# CH32F_V208W-R0.net
KiCad netlist of a schematic drawn in Altium Designer
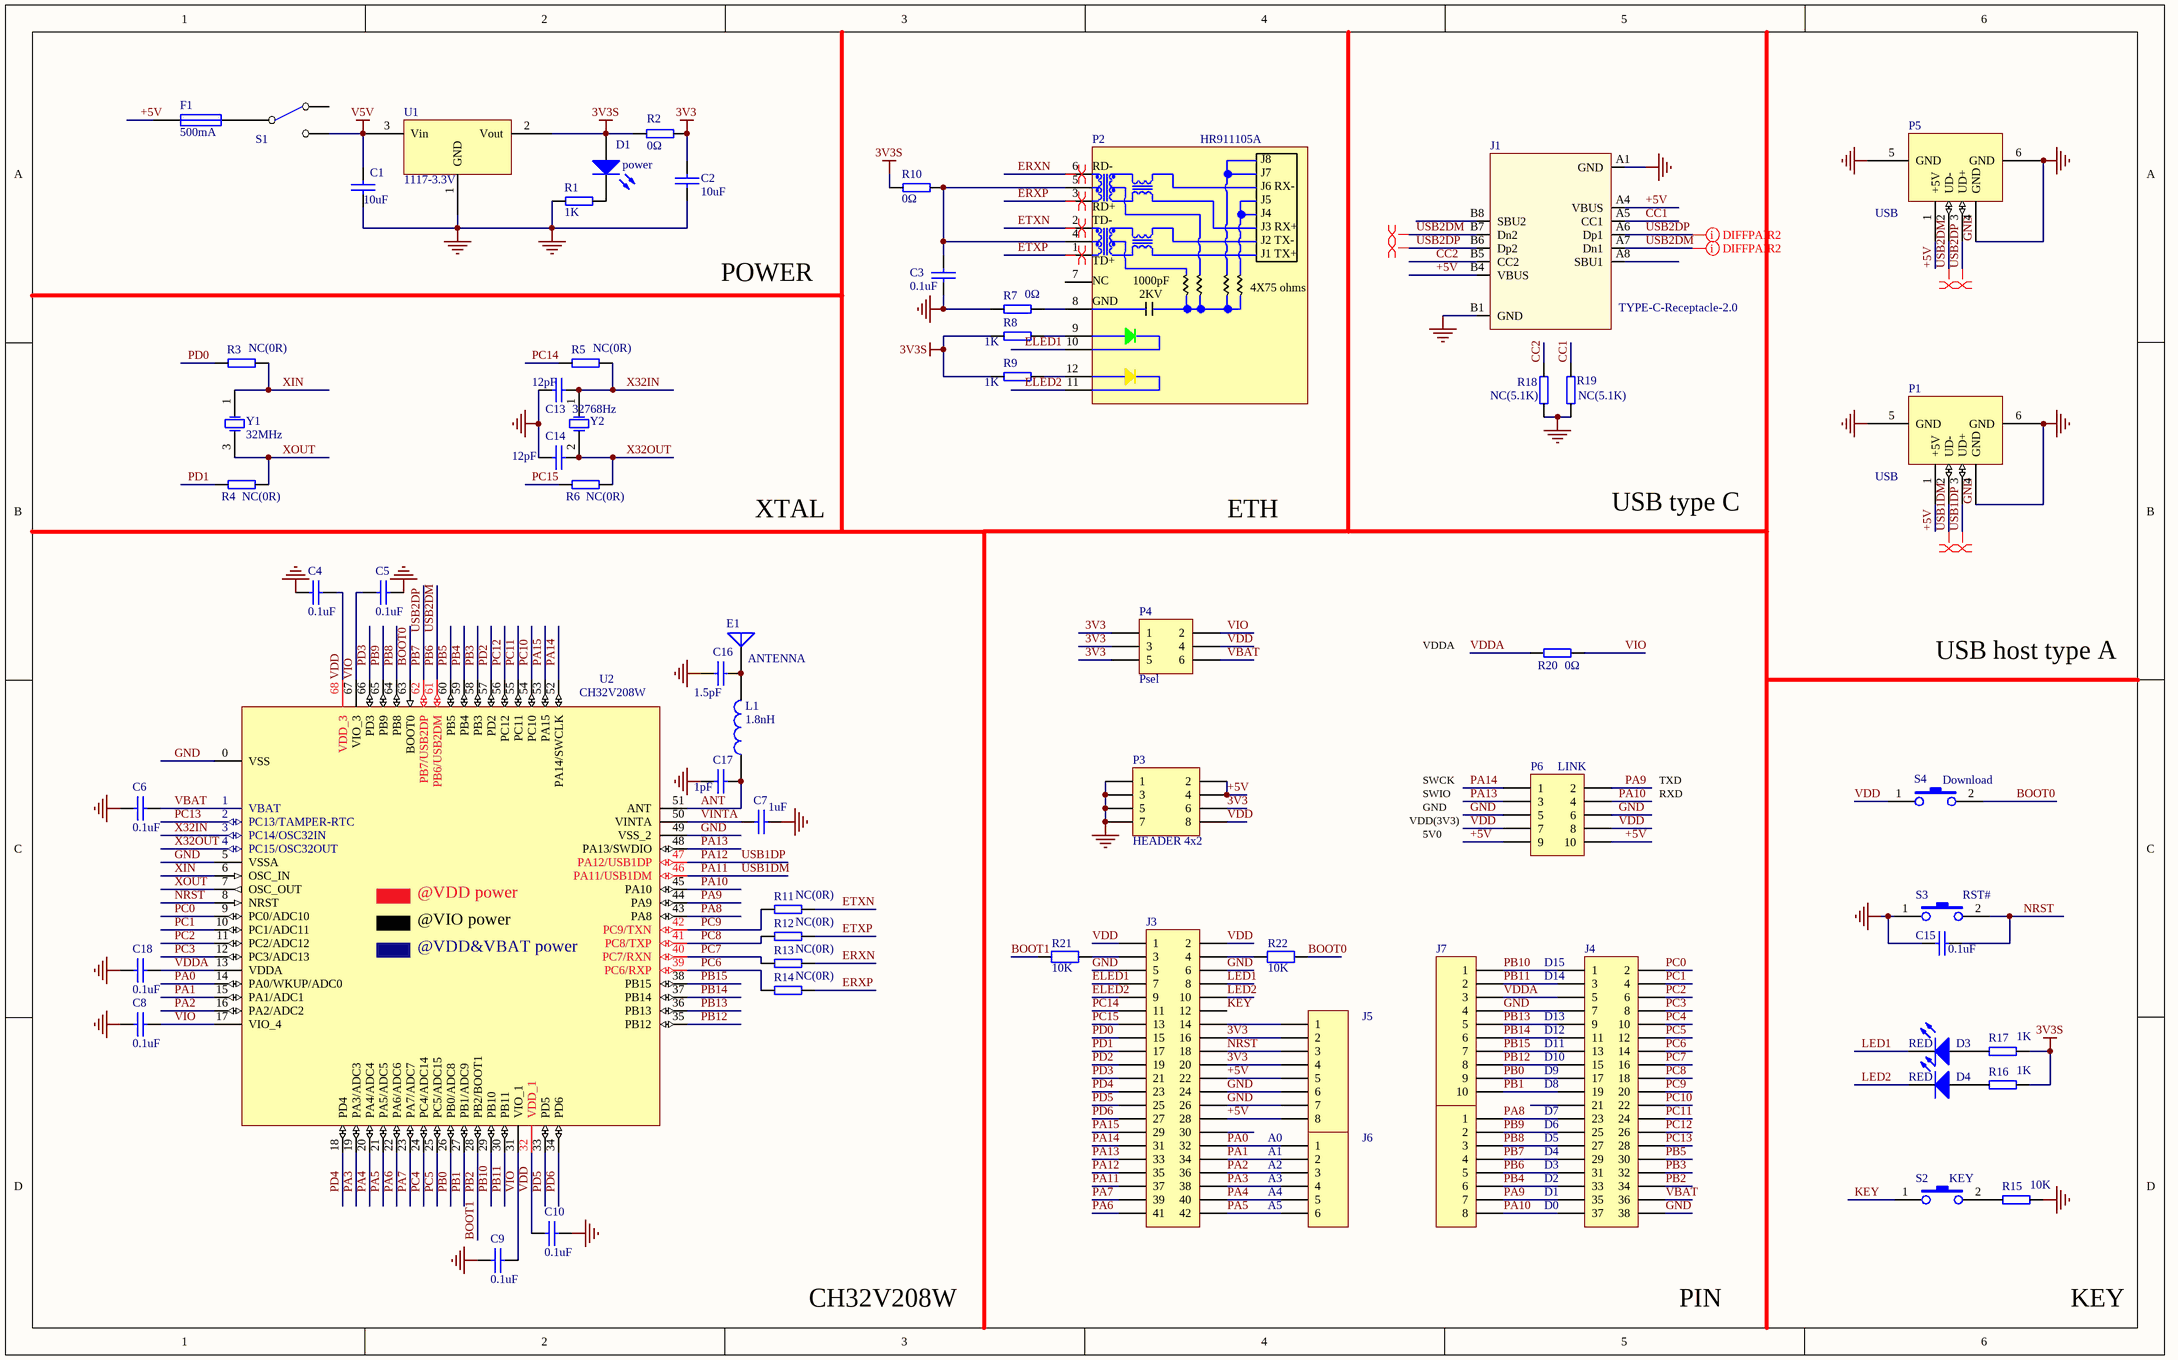
[diagram p0: CH32F&V208W-R0.SchDoc]

(export (version "E")
  (design (tool "Eeschema 10.0.6"))
  (components
    (comp (ref "C1")
      (value "10uF")
      (footprint "3216_C")
      (description "Capacitor")
      (libsource (lib "*") (part "CAP"))
    )
    (comp (ref "C2")
      (value "10uF")
      (footprint "0603_C")
      (description "Capacitor")
      (libsource (lib "*") (part "CAP"))
    )
    (comp (ref "C3")
      (value "0.1uF")
      (footprint "0603_C")
      (description "Capacitor")
      (libsource (lib "*") (part "CAP"))
    )
    (comp (ref "C4")
      (value "0.1uF")
      (footprint "0603_C")
      (description "Capacitor")
      (libsource (lib "") (part "CAP_1"))
    )
    (comp (ref "C5")
      (value "0.1uF")
      (footprint "0603_C")
      (description "Capacitor")
      (libsource (lib "") (part "CAP_1"))
    )
    (comp (ref "C6")
      (value "0.1uF")
      (footprint "0603_C")
      (description "Capacitor")
      (libsource (lib "") (part "CAP_1"))
    )
    (comp (ref "C7")
      (value "1uF")
      (footprint "0603_C")
      (description "Capacitor")
      (libsource (lib "") (part "CAP_1"))
    )
    (comp (ref "C8")
      (value "0.1uF")
      (footprint "0603_C")
      (description "Capacitor")
      (libsource (lib "") (part "CAP_1"))
    )
    (comp (ref "C9")
      (value "0.1uF")
      (footprint "0603_C")
      (description "Capacitor")
      (libsource (lib "") (part "CAP_1"))
    )
    (comp (ref "C10")
      (value "0.1uF")
      (footprint "0603_C")
      (description "Capacitor")
      (libsource (lib "") (part "CAP_1"))
    )
    (comp (ref "C13")
      (value "12pF")
      (footprint "0603_C")
      (description "Capacitor")
      (libsource (lib "*") (part "CAP"))
    )
    (comp (ref "C14")
      (value "12pF")
      (footprint "0603_C")
      (description "Capacitor")
      (libsource (lib "*") (part "CAP"))
    )
    (comp (ref "C15")
      (value "0.1uF")
      (footprint "0603_C")
      (description "Capacitor")
      (libsource (lib "") (part "CAP_1"))
    )
    (comp (ref "C16")
      (value "1.5pF")
      (footprint "0603_C")
      (description "Capacitor")
      (libsource (lib "") (part "CAP_1"))
    )
    (comp (ref "C17")
      (value "1pF")
      (footprint "0603_C")
      (description "Capacitor")
      (libsource (lib "") (part "CAP_1"))
    )
    (comp (ref "C18")
      (value "0.1uF")
      (footprint "0603_C")
      (description "Capacitor")
      (libsource (lib "") (part "CAP_1"))
    )
    (comp (ref "D1")
      (value "power")
      (footprint "0603+")
      (description "Typical INFRARED GaAs LED")
      (fields (field (name "PUBLISHER") "Altium Limited"))
      (libsource (lib "*") (part "LED0"))
    )
    (comp (ref "D3")
      (value "RED")
      (footprint "0603+")
      (description "Typical INFRARED GaAs LED")
      (fields (field (name "PUBLISHER") "Altium Limited"))
      (libsource (lib "*") (part "LED0"))
    )
    (comp (ref "D4")
      (value "RED")
      (footprint "0603+")
      (description "Typical INFRARED GaAs LED")
      (fields (field (name "PUBLISHER") "Altium Limited"))
      (libsource (lib "*") (part "LED0"))
    )
    (comp (ref "E1")
      (value "ANTENNA")
      (footprint "MYPCB:ANT-F-1-2.4G-1.6")
      (description "Generic Antenna")
      (libsource (lib "*") (part "ANTENNA"))
    )
    (comp (ref "F1")
      (value "500mA")
      (footprint "0603")
      (description "Fuse")
      (libsource (lib "wch_sch_others") (part "FUSE1"))
    )
    (comp (ref "J1")
      (value "TYPE-C-Receptacle-2.0")
      (footprint "TYPE-C-Receptacle-2.0")
      (description "Type-C USB2.0 母座")
      (libsource (lib "Miscellaneous SCH Lib") (part "TYPE-C-Receptacle-2.0"))
    )
    (comp (ref "J3")
      (value "Header 21X2")
      (footprint "IDC42-2.54mm")
      (description "Header, 21-Pin, Dual row")
      (fields (field (name "PUBLISHER") "Altium Limited"))
      (libsource (lib "PCB_Project") (part "Header 21X2"))
    )
    (comp (ref "J4")
      (value "Header 19X2")
      (footprint "IDC38-2.54mm")
      (description "Header, 19-Pin, Dual row")
      (fields (field (name "PUBLISHER") "Altium Limited"))
      (libsource (lib "Miscellaneous Connectors") (part "Header 19X2"))
    )
    (comp (ref "J5")
      (value "Header 8")
      (footprint "SIP8-2.54mm")
      (description "Header, 8-Pin")
      (fields (field (name "PUBLISHER") "Altium Limited"))
      (libsource (lib "Miscellaneous Connectors") (part "Header 8"))
    )
    (comp (ref "J6")
      (value "Header 6")
      (footprint "SIP6-2.54MM")
      (description "Header, 6-Pin")
      (fields (field (name "PUBLISHER") "Altium Limited"))
      (libsource (lib "Miscellaneous Connectors") (part "Header 6"))
    )
    (comp (ref "J7")
      (value "Header 10")
      (footprint "SIP10-2.54mm")
      (description "Header, 10-Pin")
      (fields (field (name "PUBLISHER") "Altium Limited"))
      (libsource (lib "Miscellaneous Connectors") (part "Header 10"))
    )
    (comp (ref "J8")
      (value "Header 8")
      (footprint "SIP8-2.54mm")
      (description "Header, 8-Pin")
      (fields (field (name "PUBLISHER") "Altium Limited"))
      (libsource (lib "") (part "Header 8_1"))
    )
    (comp (ref "L1") (value "1.8nH") (footprint "0603") (libsource (lib "*") (part "INDUCTOR")))
    (comp (ref "P1")
      (value "USB")
      (footprint "USBAF")
      (description "USB Port")
      (libsource (lib "*") (part "USB"))
    )
    (comp (ref "P2") (value "HR911105A") (footprint "HR911105A") (libsource (lib "*") (part "HR911105A")))
    (comp (ref "P3")
      (value "HEADER 4x2")
      (footprint "MYPCB:IDC8-2.54mm")
      (description "Header, 4-Pin, Dual row")
      (libsource (lib "wch_sch_others") (part "HEADER 4x2"))
    )
    (comp (ref "P4")
      (value "Psel")
      (footprint "IDC6-2.54mm")
      (description "Header, 3-Pin, Dual row, Right Angle")
      (fields (field (name "PUBLISHER") "Altium Limited"))
      (libsource (lib "Miscellaneous Connectors") (part "Header 3X2H"))
    )
    (comp (ref "P5")
      (value "USB")
      (footprint "USBAF")
      (description "USB Port")
      (libsource (lib "*") (part "USB"))
    )
    (comp (ref "P6")
      (value "LINK")
      (footprint "IDC10-2.54mm")
      (description "Header, 5-Pin, Dual row, Right Angle")
      (fields (field (name "PUBLISHER") "Altium Limited"))
      (libsource (lib "Miscellaneous Connectors") (part "Header 5X2H"))
    )
    (comp (ref "R1") (value "1K") (footprint "0603") (libsource (lib "wch_sch_others") (part "RES")))
    (comp (ref "R2") (value "0Ω") (footprint "0603") (libsource (lib "wch_sch_others") (part "RES")))
    (comp (ref "R3") (value "NC(0R)") (footprint "0603") (libsource (lib "wch_sch_others") (part "RES")))
    (comp (ref "R4") (value "NC(0R)") (footprint "0603") (libsource (lib "wch_sch_others") (part "RES")))
    (comp (ref "R5") (value "NC(0R)") (footprint "0603") (libsource (lib "wch_sch_others") (part "RES")))
    (comp (ref "R6") (value "NC(0R)") (footprint "0603") (libsource (lib "wch_sch_others") (part "RES")))
    (comp (ref "R7") (value "0Ω") (footprint "0603") (libsource (lib "wch_sch_others") (part "RES")))
    (comp (ref "R8") (value "1K") (footprint "0603") (libsource (lib "wch_sch_others") (part "RES")))
    (comp (ref "R9") (value "1K") (footprint "0603") (libsource (lib "wch_sch_others") (part "RES")))
    (comp (ref "R10") (value "0Ω") (footprint "0603") (libsource (lib "wch_sch_others") (part "RES")))
    (comp (ref "R11") (value "NC(0R)") (footprint "0603") (libsource (lib "wch_sch_others") (part "RES")))
    (comp (ref "R12") (value "NC(0R)") (footprint "0603") (libsource (lib "wch_sch_others") (part "RES")))
    (comp (ref "R13") (value "NC(0R)") (footprint "0603") (libsource (lib "wch_sch_others") (part "RES")))
    (comp (ref "R14") (value "NC(0R)") (footprint "0603") (libsource (lib "wch_sch_others") (part "RES")))
    (comp (ref "R15") (value "10K") (footprint "0603") (libsource (lib "wch_sch_others") (part "RES")))
    (comp (ref "R16") (value "1K") (footprint "0603") (libsource (lib "wch_sch_others") (part "RES")))
    (comp (ref "R17") (value "1K") (footprint "0603") (libsource (lib "wch_sch_others") (part "RES")))
    (comp (ref "R18") (value "NC(5.1K)") (footprint "0603") (libsource (lib "wch_sch_others") (part "RES")))
    (comp (ref "R19") (value "NC(5.1K)") (footprint "0603") (libsource (lib "wch_sch_others") (part "RES")))
    (comp (ref "R20") (value "0Ω") (footprint "0603") (libsource (lib "*") (part "R")))
    (comp (ref "R21")
      (value "10K")
      (footprint "0603")
      (description "Resistor")
      (libsource (lib "Miscellaneous Devices") (part "Res2"))
    )
    (comp (ref "R22")
      (value "10K")
      (footprint "0603")
      (description "Resistor")
      (libsource (lib "Miscellaneous Devices") (part "Res2"))
    )
    (comp (ref "S1") (value "SW SPDT") (footprint "KEY_B") (libsource (lib "*") (part "SW SPDT")))
    (comp (ref "S2")
      (value "KEY")
      (footprint "SMD_6.1x3.65x2.5mm-KEY")
      (libsource (lib "wch_sch_others") (part "KEY1"))
    )
    (comp (ref "S3")
      (value "RST#")
      (footprint "SMD_6.1x3.65x2.5mm-KEY")
      (libsource (lib "wch_sch_others") (part "KEY1"))
    )
    (comp (ref "S4")
      (value "Download")
      (footprint "SMD_6.1x3.65x2.5mm-KEY")
      (libsource (lib "wch_sch_others") (part "KEY1"))
    )
    (comp (ref "U1")
      (value "1117-3.3V")
      (footprint "SOT-223")
      (libsource (lib "wch_sch_others") (part "1117-3.3V"))
    )
    (comp (ref "U2")
      (value "CH32V208W")
      (footprint "QFN68_8x8")
      (description "RISC-V BLE5.3 MCU, 10M Ethernet, 2*USB, CAN")
      (libsource (lib "CHXXX") (part "CH32V208W"))
    )
    (comp (ref "Y1")
      (value "32MHz")
      (footprint "XT3225")
      (description "Crystal Oscillator")
      (fields (field (name "PUBLISHER") "Altium Limited"))
      (libsource (lib "") (part "XTAL_1"))
    )
    (comp (ref "Y2")
      (value "32768Hz")
      (footprint "FC-135")
      (description "Crystal Oscillator")
      (fields (field (name "PUBLISHER") "Altium Limited"))
      (libsource (lib "*") (part "XTAL"))
    )
  )
  (nets
    (net (code "1") (name "/+5V") (class "Default")
      (node (ref "F1") (pin "1") (pinfunction "1_1") (pintype "passive"))
      (node (ref "J1") (pin "A4") (pinfunction "VBUS_A4") (pintype "passive"))
      (node (ref "J1") (pin "B4") (pinfunction "VBUS_B4") (pintype "passive"))
      (node (ref "J3") (pin "22") (pinfunction "22_22") (pintype "passive"))
      (node (ref "J3") (pin "28") (pinfunction "28_28") (pintype "passive"))
      (node (ref "J5") (pin "5") (pinfunction "5_5") (pintype "passive"))
      (node (ref "J5") (pin "8") (pinfunction "8_8") (pintype "passive"))
      (node (ref "P1") (pin "1") (pinfunction "+5V_1") (pintype "power_in"))
      (node (ref "P3") (pin "2") (pinfunction "2_2") (pintype "passive"))
      (node (ref "P3") (pin "4") (pinfunction "4_4") (pintype "passive"))
      (node (ref "P5") (pin "1") (pinfunction "+5V_1") (pintype "power_in"))
      (node (ref "P6") (pin "10") (pinfunction "10_10") (pintype "passive"))
      (node (ref "P6") (pin "9") (pinfunction "9_9") (pintype "passive"))
    )
    (net (code "2") (name "/ANT") (class "Default")
      (node (ref "C17") (pin "2") (pinfunction "2_2") (pintype "passive"))
      (node (ref "L1") (pin "1") (pinfunction "1_1") (pintype "passive"))
      (node (ref "U2") (pin "51") (pinfunction "ANT_51") (pintype "power_in"))
    )
    (net (code "3") (name "/BOOT0") (class "Default")
      (node (ref "R22") (pin "2") (pinfunction "2_2") (pintype "passive"))
      (node (ref "S4") (pin "2") (pinfunction "2_2") (pintype "passive"))
      (node (ref "U2") (pin "63") (pinfunction "BOOT0_63") (pintype "input"))
    )
    (net (code "4") (name "/BOOT1") (class "Default")
      (node (ref "J4") (pin "34") (pinfunction "34_34") (pintype "passive"))
      (node (ref "R21") (pin "1") (pinfunction "1_1") (pintype "passive"))
      (node (ref "U2") (pin "28") (pinfunction "PB2/BOOT1_28") (pintype "bidirectional"))
    )
    (net (code "5") (name "/CC1") (class "Default")
      (node (ref "J1") (pin "A5") (pinfunction "CC1_A5") (pintype "passive"))
      (node (ref "R19") (pin "1") (pintype "passive"))
    )
    (net (code "6") (name "/CC2") (class "Default")
      (node (ref "J1") (pin "B5") (pinfunction "CC2_B5") (pintype "passive"))
      (node (ref "R18") (pin "1") (pintype "passive"))
    )
    (net (code "7") (name "/ELED1") (class "Default")
      (node (ref "J3") (pin "7") (pinfunction "7_7") (pintype "passive"))
      (node (ref "P2") (pin "10") (pintype "passive"))
    )
    (net (code "8") (name "/ELED2") (class "Default")
      (node (ref "J3") (pin "9") (pinfunction "9_9") (pintype "passive"))
      (node (ref "P2") (pin "11") (pintype "passive"))
    )
    (net (code "9") (name "/ERXN") (class "Default")
      (node (ref "P2") (pin "6") (pintype "passive"))
      (node (ref "R13") (pin "2") (pintype "passive"))
    )
    (net (code "10") (name "/ERXP") (class "Default")
      (node (ref "P2") (pin "3") (pintype "passive"))
      (node (ref "R14") (pin "2") (pintype "passive"))
    )
    (net (code "11") (name "/ETXN") (class "Default")
      (node (ref "P2") (pin "2") (pintype "passive"))
      (node (ref "R11") (pin "2") (pintype "passive"))
    )
    (net (code "12") (name "/ETXP") (class "Default")
      (node (ref "P2") (pin "1") (pintype "passive"))
      (node (ref "R12") (pin "2") (pintype "passive"))
    )
    (net (code "13") (name "/KEY") (class "Default")
      (node (ref "J3") (pin "12") (pinfunction "12_12") (pintype "passive"))
      (node (ref "S2") (pin "1") (pinfunction "1_1") (pintype "passive"))
    )
    (net (code "14") (name "/LED1") (class "Default")
      (node (ref "D3") (pin "2") (pinfunction "K_2") (pintype "passive"))
      (node (ref "J3") (pin "8") (pinfunction "8_8") (pintype "passive"))
    )
    (net (code "15") (name "/LED2") (class "Default")
      (node (ref "D4") (pin "2") (pinfunction "K_2") (pintype "passive"))
      (node (ref "J3") (pin "10") (pinfunction "10_10") (pintype "passive"))
    )
    (net (code "16") (name "/NRST") (class "Default")
      (node (ref "C15") (pin "2") (pinfunction "2_2") (pintype "passive"))
      (node (ref "J3") (pin "18") (pinfunction "18_18") (pintype "passive"))
      (node (ref "J5") (pin "3") (pinfunction "3_3") (pintype "passive"))
      (node (ref "S3") (pin "2") (pinfunction "2_2") (pintype "passive"))
      (node (ref "U2") (pin "8") (pinfunction "NRST_8") (pintype "input"))
    )
    (net (code "17") (name "/PA0") (class "Default")
      (node (ref "J3") (pin "32") (pinfunction "32_32") (pintype "passive"))
      (node (ref "J6") (pin "1") (pinfunction "1_1") (pintype "passive"))
      (node (ref "U2") (pin "14") (pinfunction "PA0/WKUP/ADC0_14") (pintype "bidirectional"))
    )
    (net (code "18") (name "/PA1") (class "Default")
      (node (ref "J3") (pin "34") (pinfunction "34_34") (pintype "passive"))
      (node (ref "J6") (pin "2") (pinfunction "2_2") (pintype "passive"))
      (node (ref "U2") (pin "15") (pinfunction "PA1/ADC1_15") (pintype "bidirectional"))
    )
    (net (code "19") (name "/PA2") (class "Default")
      (node (ref "J3") (pin "36") (pinfunction "36_36") (pintype "passive"))
      (node (ref "J6") (pin "3") (pinfunction "3_3") (pintype "passive"))
      (node (ref "U2") (pin "16") (pinfunction "PA2/ADC2_16") (pintype "bidirectional"))
    )
    (net (code "20") (name "/PA3") (class "Default")
      (node (ref "J3") (pin "38") (pinfunction "38_38") (pintype "passive"))
      (node (ref "J6") (pin "4") (pinfunction "4_4") (pintype "passive"))
      (node (ref "U2") (pin "19") (pinfunction "PA3/ADC3_19") (pintype "bidirectional"))
    )
    (net (code "21") (name "/PA4") (class "Default")
      (node (ref "J3") (pin "40") (pinfunction "40_40") (pintype "passive"))
      (node (ref "J6") (pin "5") (pinfunction "5_5") (pintype "passive"))
      (node (ref "U2") (pin "20") (pinfunction "PA4/ADC4_20") (pintype "bidirectional"))
    )
    (net (code "22") (name "/PA5") (class "Default")
      (node (ref "J3") (pin "42") (pinfunction "42_42") (pintype "passive"))
      (node (ref "J6") (pin "6") (pinfunction "6_6") (pintype "passive"))
      (node (ref "U2") (pin "21") (pinfunction "PA5/ADC5_21") (pintype "bidirectional"))
    )
    (net (code "23") (name "/PA6") (class "Default")
      (node (ref "J3") (pin "41") (pinfunction "41_41") (pintype "passive"))
      (node (ref "U2") (pin "22") (pinfunction "PA6/ADC6_22") (pintype "bidirectional"))
    )
    (net (code "24") (name "/PA7") (class "Default")
      (node (ref "J3") (pin "39") (pinfunction "39_39") (pintype "passive"))
      (node (ref "U2") (pin "23") (pinfunction "PA7/ADC7_23") (pintype "bidirectional"))
    )
    (net (code "25") (name "/PA8") (class "Default")
      (node (ref "J4") (pin "23") (pinfunction "23_23") (pintype "passive"))
      (node (ref "J8") (pin "1") (pinfunction "1_1") (pintype "passive"))
      (node (ref "U2") (pin "43") (pinfunction "PA8_43") (pintype "bidirectional"))
    )
    (net (code "26") (name "/PA9") (class "Default")
      (node (ref "J4") (pin "35") (pinfunction "35_35") (pintype "passive"))
      (node (ref "J8") (pin "7") (pinfunction "7_7") (pintype "passive"))
      (node (ref "P6") (pin "2") (pinfunction "2_2") (pintype "passive"))
      (node (ref "U2") (pin "44") (pinfunction "PA9_44") (pintype "bidirectional"))
    )
    (net (code "27") (name "/PA10") (class "Default")
      (node (ref "J4") (pin "37") (pinfunction "37_37") (pintype "passive"))
      (node (ref "J8") (pin "8") (pinfunction "8_8") (pintype "passive"))
      (node (ref "P6") (pin "4") (pinfunction "4_4") (pintype "passive"))
      (node (ref "U2") (pin "45") (pinfunction "PA10_45") (pintype "bidirectional"))
    )
    (net (code "28") (name "/PA11") (class "Default")
      (node (ref "J3") (pin "37") (pinfunction "37_37") (pintype "passive"))
      (node (ref "P1") (pin "2") (pinfunction "UD-_2") (pintype "bidirectional"))
      (node (ref "U2") (pin "46") (pinfunction "PA11/USB1DM_46") (pintype "bidirectional"))
    )
    (net (code "29") (name "/PA12") (class "Default")
      (node (ref "J3") (pin "35") (pinfunction "35_35") (pintype "passive"))
      (node (ref "P1") (pin "3") (pinfunction "UD+_3") (pintype "bidirectional"))
      (node (ref "U2") (pin "47") (pinfunction "PA12/USB1DP_47") (pintype "bidirectional"))
    )
    (net (code "30") (name "/PA13") (class "Default")
      (node (ref "J3") (pin "33") (pinfunction "33_33") (pintype "passive"))
      (node (ref "P6") (pin "3") (pinfunction "3_3") (pintype "passive"))
      (node (ref "U2") (pin "48") (pinfunction "PA13/SWDIO_48") (pintype "bidirectional"))
    )
    (net (code "31") (name "/PA14") (class "Default")
      (node (ref "J3") (pin "31") (pinfunction "31_31") (pintype "passive"))
      (node (ref "P6") (pin "1") (pinfunction "1_1") (pintype "passive"))
      (node (ref "U2") (pin "52") (pinfunction "PA14/SWCLK_52") (pintype "bidirectional"))
    )
    (net (code "32") (name "/PA15") (class "Default")
      (node (ref "J3") (pin "29") (pinfunction "29_29") (pintype "passive"))
      (node (ref "U2") (pin "53") (pinfunction "PA15_53") (pintype "bidirectional"))
    )
    (net (code "33") (name "/PB0") (class "Default")
      (node (ref "J4") (pin "17") (pinfunction "17_17") (pintype "passive"))
      (node (ref "J7") (pin "9") (pinfunction "9_9") (pintype "passive"))
      (node (ref "U2") (pin "26") (pinfunction "PB0/ADC8_26") (pintype "bidirectional"))
    )
    (net (code "34") (name "/PB1") (class "Default")
      (node (ref "J4") (pin "19") (pinfunction "19_19") (pintype "passive"))
      (node (ref "J7") (pin "10") (pinfunction "10_10") (pintype "passive"))
      (node (ref "U2") (pin "27") (pinfunction "PB1/ADC9_27") (pintype "bidirectional"))
    )
    (net (code "35") (name "/PB3") (class "Default")
      (node (ref "J4") (pin "32") (pinfunction "32_32") (pintype "passive"))
      (node (ref "U2") (pin "58") (pinfunction "PB3_58") (pintype "bidirectional"))
    )
    (net (code "36") (name "/PB4") (class "Default")
      (node (ref "J4") (pin "33") (pinfunction "33_33") (pintype "passive"))
      (node (ref "J8") (pin "6") (pinfunction "6_6") (pintype "passive"))
      (node (ref "U2") (pin "59") (pinfunction "PB4_59") (pintype "bidirectional"))
    )
    (net (code "37") (name "/PB5") (class "Default")
      (node (ref "J4") (pin "30") (pinfunction "30_30") (pintype "passive"))
      (node (ref "U2") (pin "60") (pinfunction "PB5_60") (pintype "bidirectional"))
    )
    (net (code "38") (name "/PB6") (class "Default")
      (node (ref "J1") (pin "A7") (pinfunction "Dn1_A7") (pintype "passive"))
      (node (ref "J1") (pin "B7") (pinfunction "Dn2_B7") (pintype "passive"))
      (node (ref "J4") (pin "31") (pinfunction "31_31") (pintype "passive"))
      (node (ref "J8") (pin "5") (pinfunction "5_5") (pintype "passive"))
      (node (ref "P5") (pin "2") (pinfunction "UD-_2") (pintype "bidirectional"))
      (node (ref "U2") (pin "61") (pinfunction "PB6/USB2DM_61") (pintype "bidirectional"))
    )
    (net (code "39") (name "/PB7") (class "Default")
      (node (ref "J1") (pin "A6") (pinfunction "Dp1_A6") (pintype "passive"))
      (node (ref "J1") (pin "B6") (pinfunction "Dp2_B6") (pintype "passive"))
      (node (ref "J4") (pin "29") (pinfunction "29_29") (pintype "passive"))
      (node (ref "J8") (pin "4") (pinfunction "4_4") (pintype "passive"))
      (node (ref "P5") (pin "3") (pinfunction "UD+_3") (pintype "bidirectional"))
      (node (ref "U2") (pin "62") (pinfunction "PB7/USB2DP_62") (pintype "bidirectional"))
    )
    (net (code "40") (name "/PB8") (class "Default")
      (node (ref "J4") (pin "27") (pinfunction "27_27") (pintype "passive"))
      (node (ref "J8") (pin "3") (pinfunction "3_3") (pintype "passive"))
      (node (ref "U2") (pin "64") (pinfunction "PB8_64") (pintype "bidirectional"))
    )
    (net (code "41") (name "/PB9") (class "Default")
      (node (ref "J4") (pin "25") (pinfunction "25_25") (pintype "passive"))
      (node (ref "J8") (pin "2") (pinfunction "2_2") (pintype "passive"))
      (node (ref "U2") (pin "65") (pinfunction "PB9_65") (pintype "bidirectional"))
    )
    (net (code "42") (name "/PB10") (class "Default")
      (node (ref "J4") (pin "1") (pinfunction "1_1") (pintype "passive"))
      (node (ref "J7") (pin "1") (pinfunction "1_1") (pintype "passive"))
      (node (ref "U2") (pin "29") (pinfunction "PB10_29") (pintype "bidirectional"))
    )
    (net (code "43") (name "/PB11") (class "Default")
      (node (ref "J4") (pin "3") (pinfunction "3_3") (pintype "passive"))
      (node (ref "J7") (pin "2") (pinfunction "2_2") (pintype "passive"))
      (node (ref "U2") (pin "30") (pinfunction "PB11_30") (pintype "bidirectional"))
    )
    (net (code "44") (name "/PB12") (class "Default")
      (node (ref "J4") (pin "15") (pinfunction "15_15") (pintype "passive"))
      (node (ref "J7") (pin "8") (pinfunction "8_8") (pintype "passive"))
      (node (ref "U2") (pin "35") (pinfunction "PB12_35") (pintype "bidirectional"))
    )
    (net (code "45") (name "/PB13") (class "Default")
      (node (ref "J4") (pin "9") (pinfunction "9_9") (pintype "passive"))
      (node (ref "J7") (pin "5") (pinfunction "5_5") (pintype "passive"))
      (node (ref "U2") (pin "36") (pinfunction "PB13_36") (pintype "bidirectional"))
    )
    (net (code "46") (name "/PB14") (class "Default")
      (node (ref "J4") (pin "11") (pinfunction "11_11") (pintype "passive"))
      (node (ref "J7") (pin "6") (pinfunction "6_6") (pintype "passive"))
      (node (ref "U2") (pin "37") (pinfunction "PB14_37") (pintype "bidirectional"))
    )
    (net (code "47") (name "/PB15") (class "Default")
      (node (ref "J4") (pin "13") (pinfunction "13_13") (pintype "passive"))
      (node (ref "J7") (pin "7") (pinfunction "7_7") (pintype "passive"))
      (node (ref "U2") (pin "38") (pinfunction "PB15_38") (pintype "bidirectional"))
    )
    (net (code "48") (name "/PC0") (class "Default")
      (node (ref "J4") (pin "2") (pinfunction "2_2") (pintype "passive"))
      (node (ref "U2") (pin "9") (pinfunction "PC0/ADC10_9") (pintype "bidirectional"))
    )
    (net (code "49") (name "/PC1") (class "Default")
      (node (ref "J4") (pin "4") (pinfunction "4_4") (pintype "passive"))
      (node (ref "U2") (pin "10") (pinfunction "PC1/ADC11_10") (pintype "bidirectional"))
    )
    (net (code "50") (name "/PC2") (class "Default")
      (node (ref "J4") (pin "6") (pinfunction "6_6") (pintype "passive"))
      (node (ref "U2") (pin "11") (pinfunction "PC2/ADC12_11") (pintype "bidirectional"))
    )
    (net (code "51") (name "/PC3") (class "Default")
      (node (ref "J4") (pin "8") (pinfunction "8_8") (pintype "passive"))
      (node (ref "U2") (pin "12") (pinfunction "PC3/ADC13_12") (pintype "bidirectional"))
    )
    (net (code "52") (name "/PC4") (class "Default")
      (node (ref "J4") (pin "10") (pinfunction "10_10") (pintype "passive"))
      (node (ref "U2") (pin "24") (pinfunction "PC4/ADC14_24") (pintype "bidirectional"))
    )
    (net (code "53") (name "/PC5") (class "Default")
      (node (ref "J4") (pin "12") (pinfunction "12_12") (pintype "passive"))
      (node (ref "U2") (pin "25") (pinfunction "PC5/ADC15_25") (pintype "bidirectional"))
    )
    (net (code "54") (name "/PC6") (class "Default")
      (node (ref "J4") (pin "14") (pinfunction "14_14") (pintype "passive"))
      (node (ref "R14") (pin "1") (pintype "passive"))
      (node (ref "U2") (pin "39") (pinfunction "PC6/RXP_39") (pintype "bidirectional"))
    )
    (net (code "55") (name "/PC7") (class "Default")
      (node (ref "J4") (pin "16") (pinfunction "16_16") (pintype "passive"))
      (node (ref "R13") (pin "1") (pintype "passive"))
      (node (ref "U2") (pin "40") (pinfunction "PC7/RXN_40") (pintype "bidirectional"))
    )
    (net (code "56") (name "/PC8") (class "Default")
      (node (ref "J4") (pin "18") (pinfunction "18_18") (pintype "passive"))
      (node (ref "R12") (pin "1") (pintype "passive"))
      (node (ref "U2") (pin "41") (pinfunction "PC8/TXP_41") (pintype "bidirectional"))
    )
    (net (code "57") (name "/PC9") (class "Default")
      (node (ref "J4") (pin "20") (pinfunction "20_20") (pintype "passive"))
      (node (ref "R11") (pin "1") (pintype "passive"))
      (node (ref "U2") (pin "42") (pinfunction "PC9/TXN_42") (pintype "bidirectional"))
    )
    (net (code "58") (name "/PC10") (class "Default")
      (node (ref "J4") (pin "22") (pinfunction "22_22") (pintype "passive"))
      (node (ref "U2") (pin "54") (pinfunction "PC10_54") (pintype "bidirectional"))
    )
    (net (code "59") (name "/PC11") (class "Default")
      (node (ref "J4") (pin "24") (pinfunction "24_24") (pintype "passive"))
      (node (ref "U2") (pin "55") (pinfunction "PC11_55") (pintype "bidirectional"))
    )
    (net (code "60") (name "/PC12") (class "Default")
      (node (ref "J4") (pin "26") (pinfunction "26_26") (pintype "passive"))
      (node (ref "U2") (pin "56") (pinfunction "PC12_56") (pintype "bidirectional"))
    )
    (net (code "61") (name "/PC13") (class "Default")
      (node (ref "J4") (pin "28") (pinfunction "28_28") (pintype "passive"))
      (node (ref "U2") (pin "2") (pinfunction "PC13/TAMPER-RTC_2") (pintype "bidirectional"))
    )
    (net (code "62") (name "/PC14") (class "Default")
      (node (ref "J3") (pin "11") (pinfunction "11_11") (pintype "passive"))
      (node (ref "R5") (pin "1") (pintype "passive"))
    )
    (net (code "63") (name "/PC15") (class "Default")
      (node (ref "J3") (pin "13") (pinfunction "13_13") (pintype "passive"))
      (node (ref "R6") (pin "1") (pintype "passive"))
    )
    (net (code "64") (name "/PD0") (class "Default")
      (node (ref "J3") (pin "15") (pinfunction "15_15") (pintype "passive"))
      (node (ref "R3") (pin "1") (pintype "passive"))
    )
    (net (code "65") (name "/PD1") (class "Default")
      (node (ref "J3") (pin "17") (pinfunction "17_17") (pintype "passive"))
      (node (ref "R4") (pin "1") (pintype "passive"))
    )
    (net (code "66") (name "/PD2") (class "Default")
      (node (ref "J3") (pin "19") (pinfunction "19_19") (pintype "passive"))
      (node (ref "U2") (pin "57") (pinfunction "PD2_57") (pintype "bidirectional"))
    )
    (net (code "67") (name "/PD3") (class "Default")
      (node (ref "J3") (pin "21") (pinfunction "21_21") (pintype "passive"))
      (node (ref "U2") (pin "66") (pinfunction "PD3_66") (pintype "bidirectional"))
    )
    (net (code "68") (name "/PD4") (class "Default")
      (node (ref "J3") (pin "23") (pinfunction "23_23") (pintype "passive"))
      (node (ref "U2") (pin "18") (pinfunction "PD4_18") (pintype "bidirectional"))
    )
    (net (code "69") (name "/PD5") (class "Default")
      (node (ref "J3") (pin "25") (pinfunction "25_25") (pintype "passive"))
      (node (ref "U2") (pin "33") (pinfunction "PD5_33") (pintype "bidirectional"))
    )
    (net (code "70") (name "/PD6") (class "Default")
      (node (ref "J3") (pin "27") (pinfunction "27_27") (pintype "passive"))
      (node (ref "U2") (pin "34") (pinfunction "PD6_34") (pintype "bidirectional"))
    )
    (net (code "71") (name "/VBAT") (class "Default")
      (node (ref "C6") (pin "1") (pinfunction "1_1") (pintype "passive"))
      (node (ref "J4") (pin "36") (pinfunction "36_36") (pintype "passive"))
      (node (ref "P4") (pin "6") (pinfunction "6_6") (pintype "passive"))
      (node (ref "U2") (pin "1") (pinfunction "VBAT_1") (pintype "power_in"))
    )
    (net (code "72") (name "/VDD") (class "Default")
      (node (ref "C10") (pin "2") (pinfunction "2_2") (pintype "passive"))
      (node (ref "C4") (pin "1") (pinfunction "1_1") (pintype "passive"))
      (node (ref "J3") (pin "1") (pinfunction "1_1") (pintype "passive"))
      (node (ref "J3") (pin "2") (pinfunction "2_2") (pintype "passive"))
      (node (ref "P3") (pin "8") (pinfunction "8_8") (pintype "passive"))
      (node (ref "P4") (pin "4") (pinfunction "4_4") (pintype "passive"))
      (node (ref "P6") (pin "7") (pinfunction "7_7") (pintype "passive"))
      (node (ref "P6") (pin "8") (pinfunction "8_8") (pintype "passive"))
      (node (ref "S4") (pin "1") (pinfunction "1_1") (pintype "passive"))
      (node (ref "U2") (pin "32") (pinfunction "VDD_1_32") (pintype "power_in"))
      (node (ref "U2") (pin "68") (pinfunction "VDD_3_68") (pintype "power_in"))
    )
    (net (code "73") (name "/VDDA") (class "Default")
      (node (ref "C18") (pin "1") (pinfunction "1_1") (pintype "passive"))
      (node (ref "J4") (pin "5") (pinfunction "5_5") (pintype "passive"))
      (node (ref "J7") (pin "3") (pinfunction "3_3") (pintype "passive"))
      (node (ref "R20") (pin "2") (pinfunction "2_2") (pintype "passive"))
      (node (ref "U2") (pin "13") (pinfunction "VDDA_13") (pintype "power_in"))
    )
    (net (code "74") (name "/VINTA") (class "Default")
      (node (ref "C7") (pin "1") (pinfunction "1_1") (pintype "passive"))
      (node (ref "U2") (pin "50") (pinfunction "VINTA_50") (pintype "power_in"))
    )
    (net (code "75") (name "/VIO") (class "Default")
      (node (ref "C5") (pin "2") (pinfunction "2_2") (pintype "passive"))
      (node (ref "C8") (pin "1") (pinfunction "1_1") (pintype "passive"))
      (node (ref "C9") (pin "1") (pinfunction "1_1") (pintype "passive"))
      (node (ref "P4") (pin "2") (pinfunction "2_2") (pintype "passive"))
      (node (ref "R20") (pin "1") (pinfunction "1_1") (pintype "passive"))
      (node (ref "U2") (pin "17") (pinfunction "VIO_4_17") (pintype "power_in"))
      (node (ref "U2") (pin "31") (pinfunction "VIO_1_31") (pintype "power_in"))
      (node (ref "U2") (pin "67") (pinfunction "VIO_3_67") (pintype "power_in"))
    )
    (net (code "76") (name "/X32IN") (class "Default")
      (node (ref "C13") (pin "2") (pinfunction "2_2") (pintype "passive"))
      (node (ref "R5") (pin "2") (pintype "passive"))
      (node (ref "U2") (pin "3") (pinfunction "PC14/OSC32IN_3") (pintype "bidirectional"))
      (node (ref "Y2") (pin "1") (pinfunction "OSC1_1") (pintype "passive"))
    )
    (net (code "77") (name "/X32OUT") (class "Default")
      (node (ref "C14") (pin "2") (pinfunction "2_2") (pintype "passive"))
      (node (ref "R6") (pin "2") (pintype "passive"))
      (node (ref "U2") (pin "4") (pinfunction "PC15/OSC32OUT_4") (pintype "bidirectional"))
      (node (ref "Y2") (pin "2") (pinfunction "OSC2_2") (pintype "passive"))
    )
    (net (code "78") (name "/XIN") (class "Default")
      (node (ref "R3") (pin "2") (pintype "passive"))
      (node (ref "U2") (pin "6") (pinfunction "OSC_IN_6") (pintype "input"))
      (node (ref "Y1") (pin "1") (pinfunction "OSC1_1") (pintype "passive"))
    )
    (net (code "79") (name "/XOUT") (class "Default")
      (node (ref "R4") (pin "2") (pintype "passive"))
      (node (ref "U2") (pin "7") (pinfunction "OSC_OUT_7") (pintype "output"))
      (node (ref "Y1") (pin "3") (pinfunction "OSC2_3") (pintype "passive"))
    )
    (net (code "80") (name "3V3") (class "Default")
      (node (ref "C2") (pin "1") (pinfunction "1_1") (pintype "passive"))
      (node (ref "J3") (pin "16") (pinfunction "16_16") (pintype "passive"))
      (node (ref "J3") (pin "20") (pinfunction "20_20") (pintype "passive"))
      (node (ref "J5") (pin "2") (pinfunction "2_2") (pintype "passive"))
      (node (ref "J5") (pin "4") (pinfunction "4_4") (pintype "passive"))
      (node (ref "P3") (pin "6") (pinfunction "6_6") (pintype "passive"))
      (node (ref "P4") (pin "1") (pinfunction "1_1") (pintype "passive"))
      (node (ref "P4") (pin "3") (pinfunction "3_3") (pintype "passive"))
      (node (ref "P4") (pin "5") (pinfunction "5_5") (pintype "passive"))
      (node (ref "R2") (pin "1") (pintype "passive"))
    )
    (net (code "81") (name "3V3S") (class "Default")
      (node (ref "D1") (pin "1") (pinfunction "A_1") (pintype "passive"))
      (node (ref "R10") (pin "2") (pintype "passive"))
      (node (ref "R16") (pin "1") (pintype "passive"))
      (node (ref "R17") (pin "1") (pintype "passive"))
      (node (ref "R2") (pin "2") (pintype "passive"))
      (node (ref "R8") (pin "1") (pintype "passive"))
      (node (ref "R9") (pin "1") (pintype "passive"))
      (node (ref "U1") (pin "2") (pinfunction "Vout_2") (pintype "passive"))
    )
    (net (code "82") (name "GND") (class "Default")
      (node (ref "C1") (pin "2") (pinfunction "2_2") (pintype "passive"))
      (node (ref "C10") (pin "1") (pinfunction "1_1") (pintype "passive"))
      (node (ref "C13") (pin "1") (pinfunction "1_1") (pintype "passive"))
      (node (ref "C14") (pin "1") (pinfunction "1_1") (pintype "passive"))
      (node (ref "C15") (pin "1") (pinfunction "1_1") (pintype "passive"))
      (node (ref "C16") (pin "1") (pinfunction "1_1") (pintype "passive"))
      (node (ref "C17") (pin "1") (pinfunction "1_1") (pintype "passive"))
      (node (ref "C18") (pin "2") (pinfunction "2_2") (pintype "passive"))
      (node (ref "C2") (pin "2") (pinfunction "2_2") (pintype "passive"))
      (node (ref "C3") (pin "1") (pinfunction "1_1") (pintype "passive"))
      (node (ref "C4") (pin "2") (pinfunction "2_2") (pintype "passive"))
      (node (ref "C5") (pin "1") (pinfunction "1_1") (pintype "passive"))
      (node (ref "C6") (pin "2") (pinfunction "2_2") (pintype "passive"))
      (node (ref "C7") (pin "2") (pinfunction "2_2") (pintype "passive"))
      (node (ref "C8") (pin "2") (pinfunction "2_2") (pintype "passive"))
      (node (ref "C9") (pin "2") (pinfunction "2_2") (pintype "passive"))
      (node (ref "J1") (pin "A1") (pinfunction "GND_A1") (pintype "passive"))
      (node (ref "J1") (pin "B1") (pinfunction "GND_B1") (pintype "passive"))
      (node (ref "J3") (pin "24") (pinfunction "24_24") (pintype "passive"))
      (node (ref "J3") (pin "26") (pinfunction "26_26") (pintype "passive"))
      (node (ref "J3") (pin "5") (pinfunction "5_5") (pintype "passive"))
      (node (ref "J3") (pin "6") (pinfunction "6_6") (pintype "passive"))
      (node (ref "J4") (pin "38") (pinfunction "38_38") (pintype "passive"))
      (node (ref "J4") (pin "7") (pinfunction "7_7") (pintype "passive"))
      (node (ref "J5") (pin "6") (pinfunction "6_6") (pintype "passive"))
      (node (ref "J5") (pin "7") (pinfunction "7_7") (pintype "passive"))
      (node (ref "J7") (pin "4") (pinfunction "4_4") (pintype "passive"))
      (node (ref "P1") (pin "4") (pinfunction "GND_4") (pintype "power_in"))
      (node (ref "P1") (pin "5") (pinfunction "GND_5") (pintype "power_in"))
      (node (ref "P1") (pin "6") (pinfunction "GND_6") (pintype "power_in"))
      (node (ref "P3") (pin "1") (pinfunction "1_1") (pintype "passive"))
      (node (ref "P3") (pin "3") (pinfunction "3_3") (pintype "passive"))
      (node (ref "P3") (pin "5") (pinfunction "5_5") (pintype "passive"))
      (node (ref "P3") (pin "7") (pinfunction "7_7") (pintype "passive"))
      (node (ref "P5") (pin "4") (pinfunction "GND_4") (pintype "power_in"))
      (node (ref "P5") (pin "5") (pinfunction "GND_5") (pintype "power_in"))
      (node (ref "P5") (pin "6") (pinfunction "GND_6") (pintype "power_in"))
      (node (ref "P6") (pin "5") (pinfunction "5_5") (pintype "passive"))
      (node (ref "P6") (pin "6") (pinfunction "6_6") (pintype "passive"))
      (node (ref "R1") (pin "1") (pintype "passive"))
      (node (ref "R15") (pin "1") (pintype "passive"))
      (node (ref "R18") (pin "2") (pintype "passive"))
      (node (ref "R19") (pin "2") (pintype "passive"))
      (node (ref "R7") (pin "1") (pintype "passive"))
      (node (ref "S3") (pin "1") (pinfunction "1_1") (pintype "passive"))
      (node (ref "U1") (pin "1") (pinfunction "GND_1") (pintype "passive"))
      (node (ref "U2") (pin "0") (pinfunction "VSS_0") (pintype "power_in"))
      (node (ref "U2") (pin "49") (pinfunction "VSS_2_49") (pintype "power_in"))
      (node (ref "U2") (pin "5") (pinfunction "VSSA_5") (pintype "power_in"))
    )
    (net (code "83") (name "Net-(C3-Pad2)") (class "Default")
      (node (ref "C3") (pin "2") (pinfunction "2_2") (pintype "passive"))
      (node (ref "P2") (pin "4") (pintype "passive"))
      (node (ref "P2") (pin "5") (pintype "passive"))
      (node (ref "R10") (pin "1") (pintype "passive"))
    )
    (net (code "84") (name "Net-(D1-K)") (class "Default")
      (node (ref "D1") (pin "2") (pinfunction "K_2") (pintype "passive"))
      (node (ref "R1") (pin "2") (pintype "passive"))
    )
    (net (code "85") (name "Net-(D3-A)") (class "Default")
      (node (ref "D3") (pin "1") (pinfunction "A_1") (pintype "passive"))
      (node (ref "R17") (pin "2") (pintype "passive"))
    )
    (net (code "86") (name "Net-(D4-A)") (class "Default")
      (node (ref "D4") (pin "1") (pinfunction "A_1") (pintype "passive"))
      (node (ref "R16") (pin "2") (pintype "passive"))
    )
    (net (code "87") (name "Net-(E1-A)") (class "Default")
      (node (ref "C16") (pin "2") (pinfunction "2_2") (pintype "passive"))
      (node (ref "E1") (pin "1") (pinfunction "A_1") (pintype "passive"))
      (node (ref "L1") (pin "2") (pinfunction "2_2") (pintype "passive"))
    )
    (net (code "88") (name "Net-(J3-Pad3)") (class "Default")
      (node (ref "J3") (pin "3") (pinfunction "3_3") (pintype "passive"))
      (node (ref "R21") (pin "2") (pinfunction "2_2") (pintype "passive"))
    )
    (net (code "89") (name "Net-(J3-Pad4)") (class "Default")
      (node (ref "J3") (pin "4") (pinfunction "4_4") (pintype "passive"))
      (node (ref "R22") (pin "1") (pinfunction "1_1") (pintype "passive"))
    )
    (net (code "90") (name "Net-(J3-Pad14)") (class "Default")
      (node (ref "J3") (pin "14") (pinfunction "14_14") (pintype "passive"))
      (node (ref "J5") (pin "1") (pinfunction "1_1") (pintype "passive"))
    )
    (net (code "91") (name "Net-(P2-Pad8)") (class "Default")
      (node (ref "P2") (pin "8") (pintype "passive"))
      (node (ref "R7") (pin "2") (pintype "passive"))
    )
    (net (code "92") (name "Net-(P2-Pad9)") (class "Default")
      (node (ref "P2") (pin "9") (pintype "passive"))
      (node (ref "R8") (pin "2") (pintype "passive"))
    )
    (net (code "93") (name "Net-(P2-Pad12)") (class "Default")
      (node (ref "P2") (pin "12") (pintype "passive"))
      (node (ref "R9") (pin "2") (pintype "passive"))
    )
    (net (code "94") (name "Net-(R15-Pad2)") (class "Default")
      (node (ref "R15") (pin "2") (pintype "passive"))
      (node (ref "S2") (pin "2") (pinfunction "2_2") (pintype "passive"))
    )
    (net (code "95") (name "Net-(S1-COMMON)") (class "Default")
      (node (ref "F1") (pin "2") (pinfunction "2_2") (pintype "passive"))
      (node (ref "S1") (pin "1") (pinfunction "COMMON_1") (pintype "passive"))
    )
    (net (code "96") (name "V5V") (class "Default")
      (node (ref "C1") (pin "1") (pinfunction "1_1") (pintype "passive"))
      (node (ref "S1") (pin "2") (pinfunction "NC_2") (pintype "passive"))
      (node (ref "U1") (pin "3") (pinfunction "Vin_3") (pintype "passive"))
    )
    (net (code "97") (name "unconnected-(J1-SBU1-PadA8)") (class "Default")
      (node (ref "J1") (pin "A8") (pinfunction "SBU1_A8") (pintype "passive"))
    )
    (net (code "98") (name "unconnected-(J1-SBU2-PadB8)") (class "Default")
      (node (ref "J1") (pin "B8") (pinfunction "SBU2_B8") (pintype "passive"))
    )
    (net (code "99") (name "unconnected-(J3-Pad30)") (class "Default")
      (node (ref "J3") (pin "30") (pinfunction "30_30") (pintype "passive"))
    )
    (net (code "100") (name "unconnected-(J4-Pad21)") (class "Default")
      (node (ref "J4") (pin "21") (pinfunction "21_21") (pintype "passive"))
    )
    (net (code "101") (name "unconnected-(P2-Pad7)") (class "Default")
      (node (ref "P2") (pin "7") (pintype "passive"))
    )
    (net (code "102") (name "unconnected-(S1-NO-Pad3)") (class "Default")
      (node (ref "S1") (pin "3") (pinfunction "NO_3") (pintype "passive"))
    )
  )
)
